# diwali_lights_1.net
KiCad netlist of a schematic drawn in EAGLE
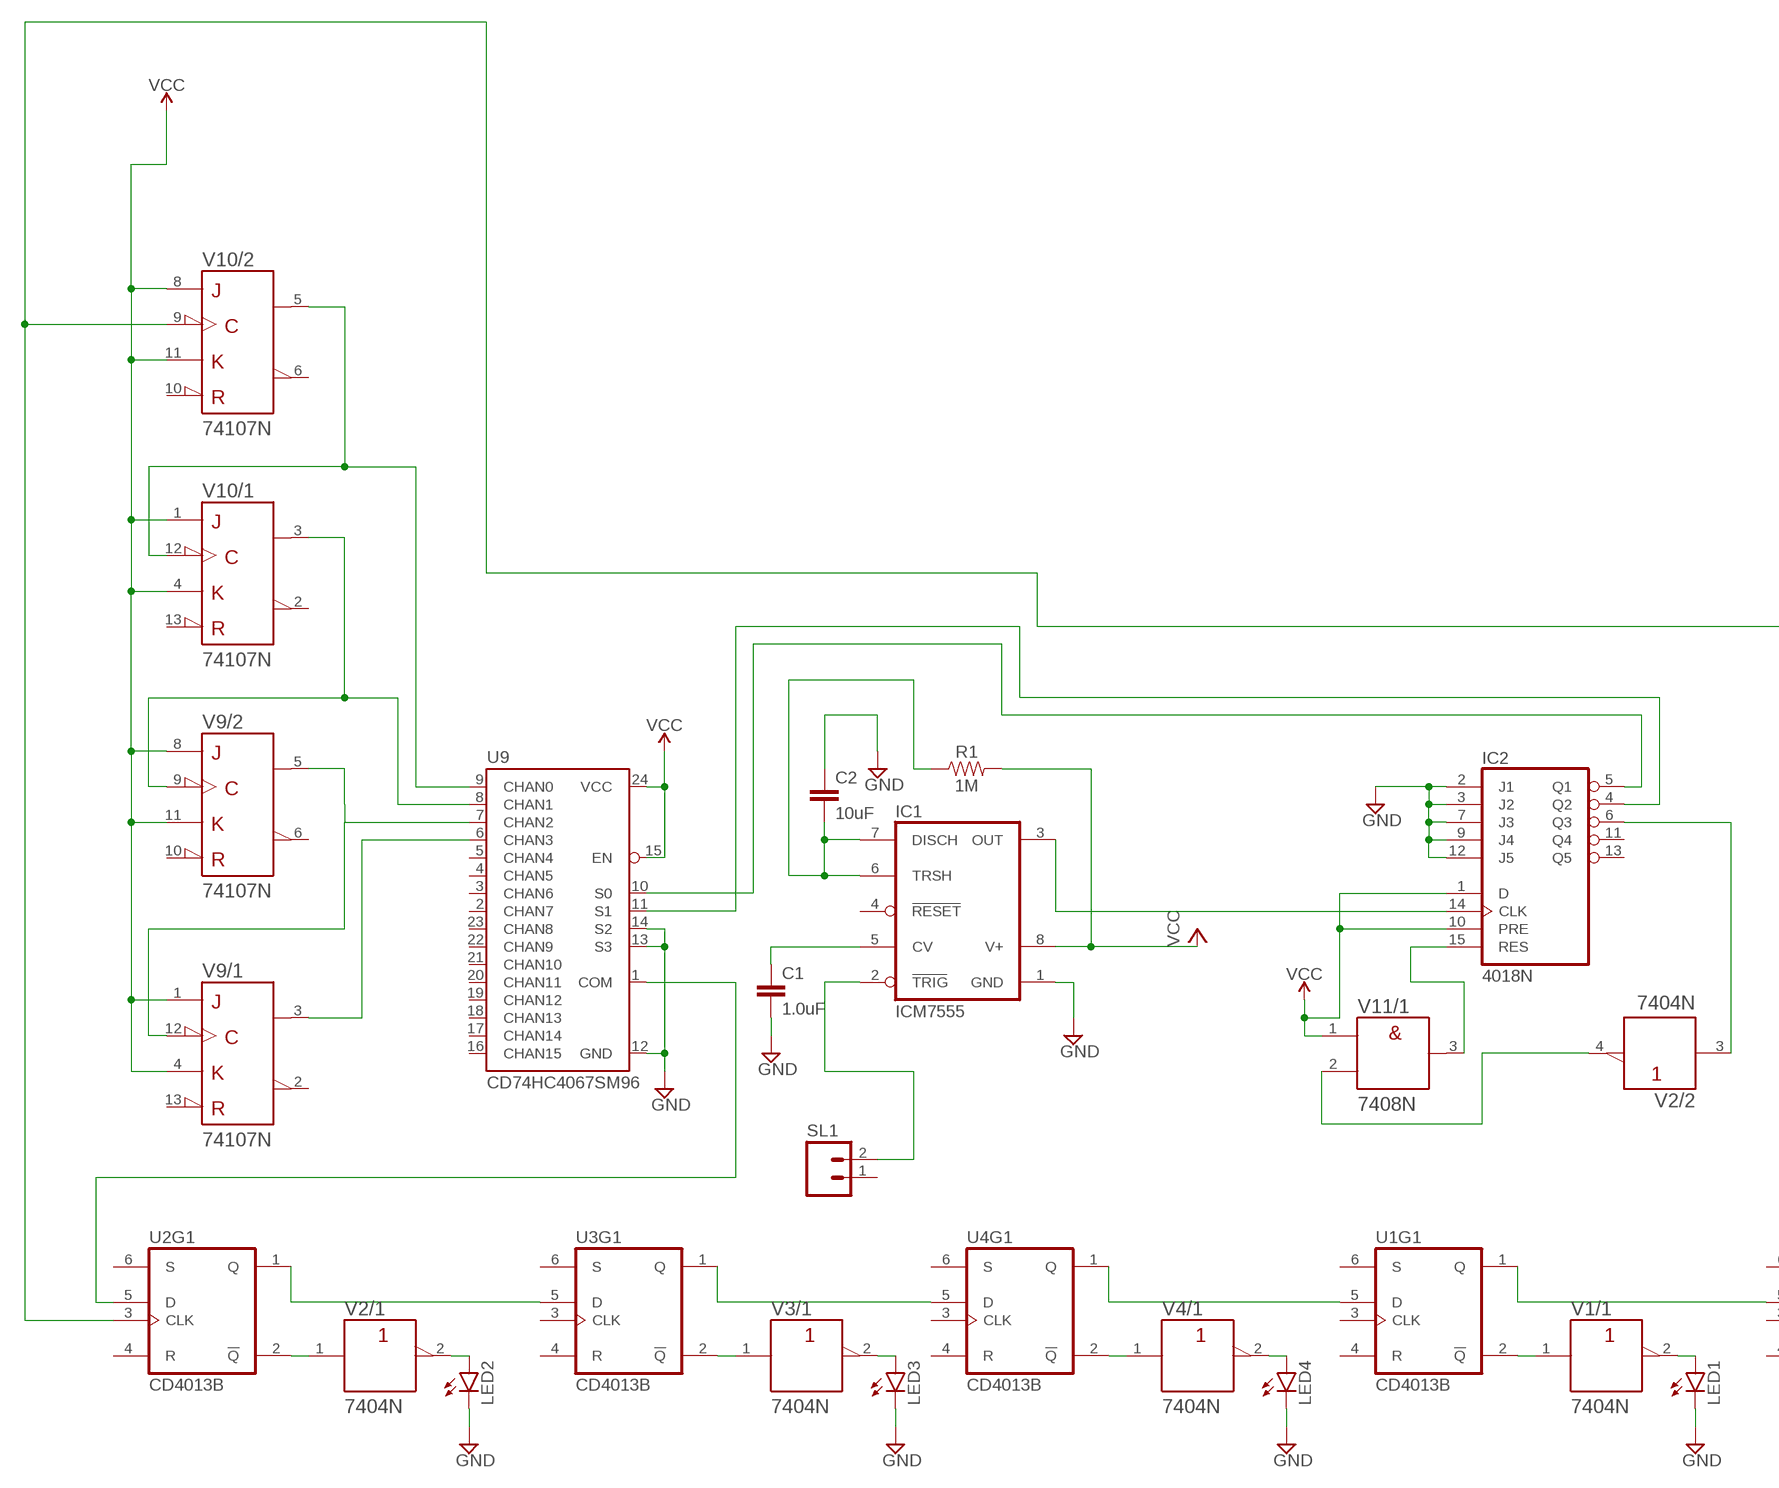
[diagram p0: schematic, sheet 1, part 1 of 2]
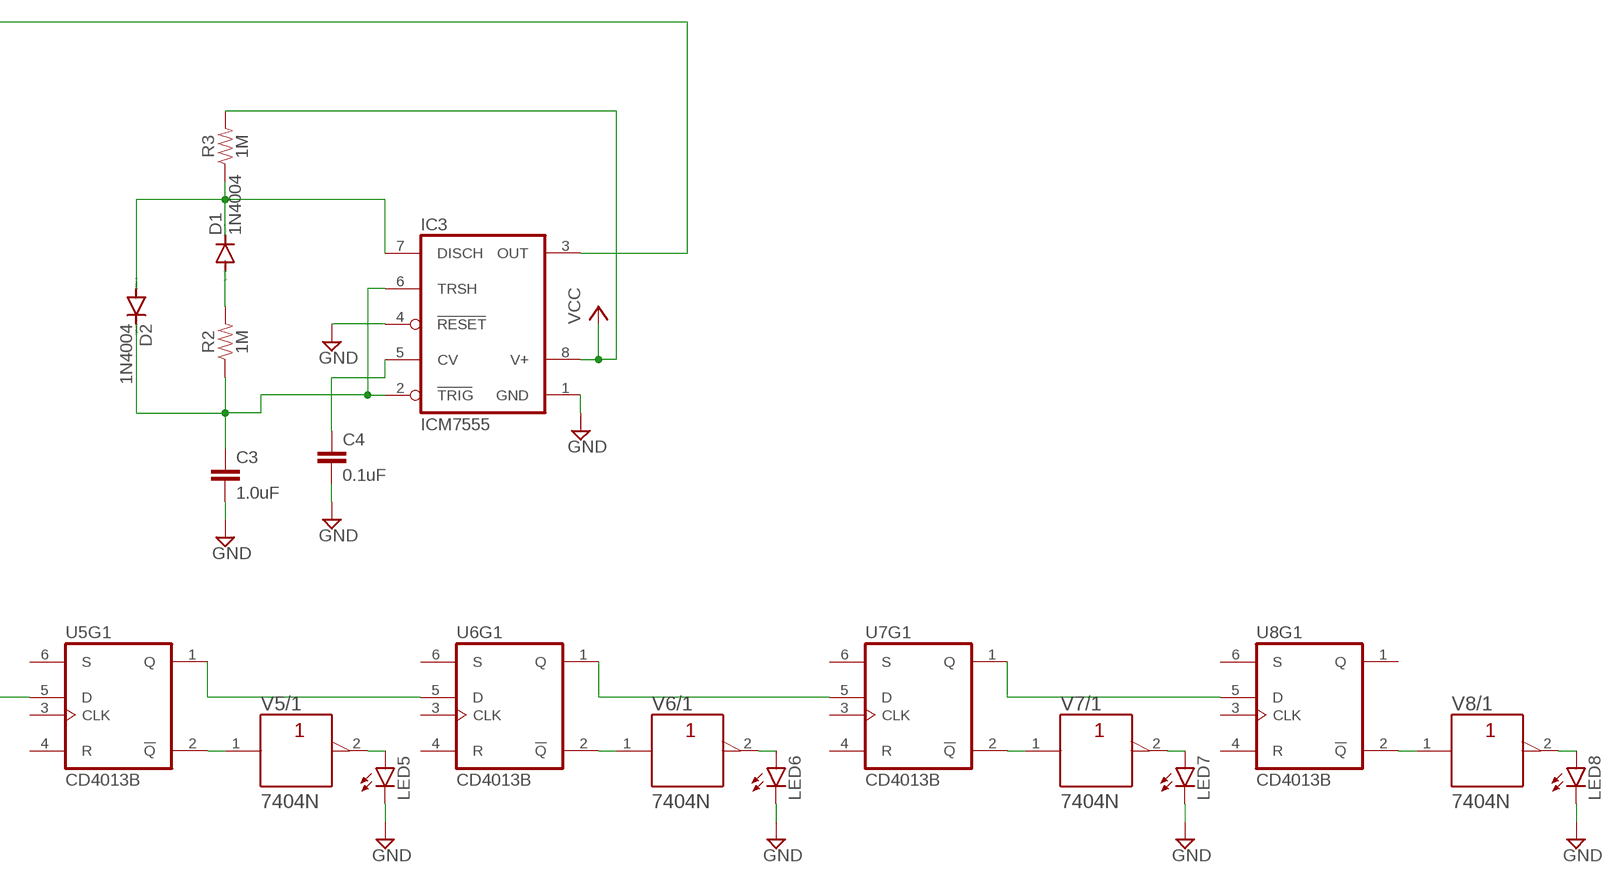
[diagram p1: schematic, sheet 1, part 2 of 2]

(export (version "E")
  (design (tool "Eeschema 10.0.6"))
  (components
    (comp (ref "C1")
      (value "1.0uF")
      (footprint "eagle-import:0402")
      (libsource (lib "eagle-import") (part "1.0UF-0402-16V-10%"))
    )
    (comp (ref "C2")
      (value "10uF")
      (footprint "eagle-import:0805")
      (libsource (lib "eagle-import") (part "10UF-0805-10V-10%"))
    )
    (comp (ref "C3")
      (value "1.0uF")
      (footprint "eagle-import:0402")
      (libsource (lib "eagle-import") (part "1.0UF-0402-16V-10%"))
    )
    (comp (ref "C4")
      (value "0.1uF")
      (footprint "eagle-import:0402")
      (libsource (lib "eagle-import") (part "0.1UF-0402-16V-10%"))
    )
    (comp (ref "D1")
      (value "1N4004")
      (footprint "eagle-import:DO41-10")
      (libsource (lib "eagle-import") (part "1N4004"))
    )
    (comp (ref "D2")
      (value "1N4004")
      (footprint "eagle-import:DO41-10")
      (libsource (lib "eagle-import") (part "1N4004"))
    )
    (comp (ref "IC1")
      (value "ICM7555")
      (footprint "eagle-import:DIL08")
      (fields (field (name "MF") "MAXIM") (field (name "MPN") "ICM7555IPA+"))
      (libsource (lib "eagle-import") (part "ICM7555"))
    )
    (comp (ref "IC2")
      (value "4018N")
      (footprint "eagle-import:DIL16")
      (libsource (lib "eagle-import") (part "4018N"))
    )
    (comp (ref "IC3")
      (value "ICM7555")
      (footprint "eagle-import:DIL08")
      (fields (field (name "MF") "MAXIM") (field (name "MPN") "ICM7555IPA+"))
      (libsource (lib "eagle-import") (part "ICM7555"))
    )
    (comp (ref "LED1")
      (value "LED5MM")
      (footprint "eagle-import:LED5MM")
      (libsource (lib "eagle-import") (part "LED5MM"))
    )
    (comp (ref "LED2")
      (value "LED5MM")
      (footprint "eagle-import:LED5MM")
      (libsource (lib "eagle-import") (part "LED5MM"))
    )
    (comp (ref "LED3")
      (value "LED5MM")
      (footprint "eagle-import:LED5MM")
      (libsource (lib "eagle-import") (part "LED5MM"))
    )
    (comp (ref "LED4")
      (value "LED5MM")
      (footprint "eagle-import:LED5MM")
      (libsource (lib "eagle-import") (part "LED5MM"))
    )
    (comp (ref "LED5")
      (value "LED5MM")
      (footprint "eagle-import:LED5MM")
      (libsource (lib "eagle-import") (part "LED5MM"))
    )
    (comp (ref "LED6")
      (value "LED5MM")
      (footprint "eagle-import:LED5MM")
      (libsource (lib "eagle-import") (part "LED5MM"))
    )
    (comp (ref "LED7")
      (value "LED5MM")
      (footprint "eagle-import:LED5MM")
      (libsource (lib "eagle-import") (part "LED5MM"))
    )
    (comp (ref "LED8")
      (value "LED5MM")
      (footprint "eagle-import:LED5MM")
      (libsource (lib "eagle-import") (part "LED5MM"))
    )
    (comp (ref "R1")
      (value "1M")
      (footprint "eagle-import:0402")
      (libsource (lib "eagle-import") (part "1MOHM-0402-1/16W-5%"))
    )
    (comp (ref "R2")
      (value "1M")
      (footprint "eagle-import:AXIAL-0.3")
      (libsource (lib "eagle-import") (part "1MOHM-HORIZ-1/4W-5%"))
    )
    (comp (ref "R3")
      (value "1M")
      (footprint "eagle-import:AXIAL-0.3")
      (libsource (lib "eagle-import") (part "1MOHM-HORIZ-1/4W-5%"))
    )
    (comp (ref "SL1")
      (value "M02")
      (footprint "eagle-import:02P")
      (libsource (lib "eagle-import") (part "M02"))
    )
    (comp (ref "U1")
      (value "CD4013B")
      (footprint "eagle-import:DIP14-KIT")
      (libsource (lib "eagle-import") (part "CD4013"))
    )
    (comp (ref "U2")
      (value "CD4013B")
      (footprint "eagle-import:DIP14-KIT")
      (libsource (lib "eagle-import") (part "CD4013"))
    )
    (comp (ref "U3")
      (value "CD4013B")
      (footprint "eagle-import:DIP14-KIT")
      (libsource (lib "eagle-import") (part "CD4013"))
    )
    (comp (ref "U4")
      (value "CD4013B")
      (footprint "eagle-import:DIP14-KIT")
      (libsource (lib "eagle-import") (part "CD4013"))
    )
    (comp (ref "U5")
      (value "CD4013B")
      (footprint "eagle-import:DIP14-KIT")
      (libsource (lib "eagle-import") (part "CD4013"))
    )
    (comp (ref "U6")
      (value "CD4013B")
      (footprint "eagle-import:DIP14-KIT")
      (libsource (lib "eagle-import") (part "CD4013"))
    )
    (comp (ref "U7")
      (value "CD4013B")
      (footprint "eagle-import:DIP14-KIT")
      (libsource (lib "eagle-import") (part "CD4013"))
    )
    (comp (ref "U8")
      (value "CD4013B")
      (footprint "eagle-import:DIP14-KIT")
      (libsource (lib "eagle-import") (part "CD4013"))
    )
    (comp (ref "U9")
      (value "CD74HC4067SM96")
      (footprint "eagle-import:SSOP24")
      (libsource (lib "eagle-import") (part "744067SM96HC"))
    )
    (comp (ref "V1")
      (value "7404N")
      (footprint "eagle-import:DIL14")
      (libsource (lib "eagle-import") (part "7404N"))
    )
    (comp (ref "V2")
      (value "7404N")
      (footprint "eagle-import:DIL14")
      (libsource (lib "eagle-import") (part "7404N"))
    )
    (comp (ref "V3")
      (value "7404N")
      (footprint "eagle-import:DIL14")
      (libsource (lib "eagle-import") (part "7404N"))
    )
    (comp (ref "V4")
      (value "7404N")
      (footprint "eagle-import:DIL14")
      (libsource (lib "eagle-import") (part "7404N"))
    )
    (comp (ref "V5")
      (value "7404N")
      (footprint "eagle-import:DIL14")
      (libsource (lib "eagle-import") (part "7404N"))
    )
    (comp (ref "V6")
      (value "7404N")
      (footprint "eagle-import:DIL14")
      (libsource (lib "eagle-import") (part "7404N"))
    )
    (comp (ref "V7")
      (value "7404N")
      (footprint "eagle-import:DIL14")
      (libsource (lib "eagle-import") (part "7404N"))
    )
    (comp (ref "V8")
      (value "7404N")
      (footprint "eagle-import:DIL14")
      (libsource (lib "eagle-import") (part "7404N"))
    )
    (comp (ref "V9")
      (value "74107N")
      (footprint "eagle-import:DIL14")
      (libsource (lib "eagle-import") (part "74107N"))
    )
    (comp (ref "V10")
      (value "74107N")
      (footprint "eagle-import:DIL14")
      (libsource (lib "eagle-import") (part "74107N"))
    )
    (comp (ref "V11")
      (value "7408N")
      (footprint "eagle-import:DIL14")
      (libsource (lib "eagle-import") (part "7408N"))
    )
  )
  (nets
    (net (code "1") (name "GND") (class "Default")
      (node (ref "C1") (pin "2") (pinfunction "2_2") (pintype "passive"))
      (node (ref "C2") (pin "1") (pinfunction "1_1") (pintype "passive"))
      (node (ref "C3") (pin "2") (pinfunction "2_2") (pintype "passive"))
      (node (ref "C4") (pin "2") (pinfunction "2_2") (pintype "passive"))
      (node (ref "IC1") (pin "1") (pinfunction "GND_1") (pintype "power_in"))
      (node (ref "IC2") (pin "12") (pinfunction "J5_12") (pintype "input"))
      (node (ref "IC2") (pin "2") (pinfunction "J1_2") (pintype "input"))
      (node (ref "IC2") (pin "3") (pinfunction "J2_3") (pintype "input"))
      (node (ref "IC2") (pin "7") (pinfunction "J3_7") (pintype "input"))
      (node (ref "IC2") (pin "9") (pinfunction "J4_9") (pintype "input"))
      (node (ref "IC3") (pin "1") (pinfunction "GND_1") (pintype "power_in"))
      (node (ref "IC3") (pin "4") (pinfunction "RESET_4") (pintype "input"))
      (node (ref "LED1") (pin "K") (pinfunction "C_K") (pintype "passive"))
      (node (ref "LED2") (pin "K") (pinfunction "C_K") (pintype "passive"))
      (node (ref "LED3") (pin "K") (pinfunction "C_K") (pintype "passive"))
      (node (ref "LED4") (pin "K") (pinfunction "C_K") (pintype "passive"))
      (node (ref "LED5") (pin "K") (pinfunction "C_K") (pintype "passive"))
      (node (ref "LED6") (pin "K") (pinfunction "C_K") (pintype "passive"))
      (node (ref "LED7") (pin "K") (pinfunction "C_K") (pintype "passive"))
      (node (ref "LED8") (pin "K") (pinfunction "C_K") (pintype "passive"))
      (node (ref "U9") (pin "12") (pinfunction "GND_12") (pintype "bidirectional"))
      (node (ref "U9") (pin "13") (pinfunction "S3_13") (pintype "input"))
      (node (ref "U9") (pin "14") (pinfunction "S2_14") (pintype "input"))
    )
    (net (code "2") (name "Net-(IC1-CV)") (class "Default")
      (node (ref "C1") (pin "1") (pinfunction "1_1") (pintype "passive"))
      (node (ref "IC1") (pin "5") (pinfunction "CV_5") (pintype "passive"))
    )
    (net (code "3") (name "Net-(IC1-DISCH)") (class "Default")
      (node (ref "C2") (pin "2") (pinfunction "2_2") (pintype "passive"))
      (node (ref "IC1") (pin "6") (pinfunction "TRSH_6") (pintype "input"))
      (node (ref "IC1") (pin "7") (pinfunction "DISCH_7") (pintype "input"))
      (node (ref "R1") (pin "1") (pinfunction "1_1") (pintype "passive"))
    )
    (net (code "4") (name "Net-(IC1-OUT)") (class "Default")
      (node (ref "IC1") (pin "3") (pinfunction "OUT_3") (pintype "output"))
      (node (ref "IC2") (pin "14") (pinfunction "CLK_14") (pintype "input"))
    )
    (net (code "5") (name "Net-(IC1-TRIG)") (class "Default")
      (node (ref "IC1") (pin "2") (pinfunction "TRIG_2") (pintype "bidirectional"))
      (node (ref "SL1") (pin "2") (pinfunction "2_2") (pintype "passive"))
    )
    (net (code "6") (name "Net-(IC2A-Q1)") (class "Default")
      (node (ref "IC2") (pin "5") (pinfunction "Q1_5") (pintype "output"))
      (node (ref "U9") (pin "10") (pinfunction "S0_10") (pintype "input"))
    )
    (net (code "7") (name "Net-(IC2A-Q2)") (class "Default")
      (node (ref "IC2") (pin "4") (pinfunction "Q2_4") (pintype "output"))
      (node (ref "U9") (pin "11") (pinfunction "S1_11") (pintype "input"))
    )
    (net (code "8") (name "Net-(IC2A-Q3)") (class "Default")
      (node (ref "IC2") (pin "6") (pinfunction "Q3_6") (pintype "output"))
      (node (ref "V2") (pin "3") (pinfunction "A_3") (pintype "input"))
    )
    (net (code "9") (name "Net-(IC2A-RES)") (class "Default")
      (node (ref "IC2") (pin "15") (pinfunction "RES_15") (pintype "input"))
      (node (ref "V11") (pin "3") (pinfunction "Y_3") (pintype "output"))
    )
    (net (code "10") (name "Net-(IC3-CV)") (class "Default")
      (node (ref "C4") (pin "1") (pinfunction "1_1") (pintype "passive"))
      (node (ref "IC3") (pin "5") (pinfunction "CV_5") (pintype "passive"))
    )
    (net (code "11") (name "Net-(IC3-DISCH)") (class "Default")
      (node (ref "D1") (pin "C") (pinfunction "C_C") (pintype "passive"))
      (node (ref "D2") (pin "A") (pinfunction "A_A") (pintype "passive"))
      (node (ref "IC3") (pin "7") (pinfunction "DISCH_7") (pintype "input"))
      (node (ref "R3") (pin "P$1") (pinfunction "1_P$1") (pintype "passive"))
    )
    (net (code "12") (name "Net-(IC3-OUT)") (class "Default")
      (node (ref "IC3") (pin "3") (pinfunction "OUT_3") (pintype "output"))
      (node (ref "U2") (pin "3") (pinfunction "CLK_3") (pintype "input"))
      (node (ref "V10") (pin "9") (pinfunction "CLK_9") (pintype "input"))
    )
    (net (code "13") (name "Net-(IC3-TRIG)") (class "Default")
      (node (ref "C3") (pin "1") (pinfunction "1_1") (pintype "passive"))
      (node (ref "D2") (pin "C") (pinfunction "C_C") (pintype "passive"))
      (node (ref "IC3") (pin "2") (pinfunction "TRIG_2") (pintype "bidirectional"))
      (node (ref "IC3") (pin "6") (pinfunction "TRSH_6") (pintype "input"))
      (node (ref "R2") (pin "P$1") (pinfunction "1_P$1") (pintype "passive"))
    )
    (net (code "14") (name "Net-(R2-2)") (class "Default")
      (node (ref "D1") (pin "A") (pinfunction "A_A") (pintype "passive"))
      (node (ref "R2") (pin "P$2") (pinfunction "2_P$2") (pintype "passive"))
    )
    (net (code "15") (name "Net-(U1A-D)") (class "Default")
      (node (ref "U1") (pin "5") (pinfunction "D_5") (pintype "input"))
      (node (ref "U4") (pin "1") (pinfunction "Q_1") (pintype "output"))
    )
    (net (code "16") (name "Net-(U1A-Q)") (class "Default")
      (node (ref "U1") (pin "1") (pinfunction "Q_1") (pintype "output"))
      (node (ref "U5") (pin "5") (pinfunction "D_5") (pintype "input"))
    )
    (net (code "17") (name "Net-(U1A-~{Q})") (class "Default")
      (node (ref "U1") (pin "2") (pinfunction "~{Q}_2") (pintype "output"))
      (node (ref "V1") (pin "1") (pinfunction "A_1") (pintype "input"))
    )
    (net (code "18") (name "Net-(U2A-D)") (class "Default")
      (node (ref "U2") (pin "5") (pinfunction "D_5") (pintype "input"))
      (node (ref "U9") (pin "1") (pinfunction "COM_1") (pintype "bidirectional"))
    )
    (net (code "19") (name "Net-(U2A-Q)") (class "Default")
      (node (ref "U2") (pin "1") (pinfunction "Q_1") (pintype "output"))
      (node (ref "U3") (pin "5") (pinfunction "D_5") (pintype "input"))
    )
    (net (code "20") (name "Net-(U2A-~{Q})") (class "Default")
      (node (ref "U2") (pin "2") (pinfunction "~{Q}_2") (pintype "output"))
      (node (ref "V2") (pin "1") (pinfunction "A_1") (pintype "input"))
    )
    (net (code "21") (name "Net-(U3A-Q)") (class "Default")
      (node (ref "U3") (pin "1") (pinfunction "Q_1") (pintype "output"))
      (node (ref "U4") (pin "5") (pinfunction "D_5") (pintype "input"))
    )
    (net (code "22") (name "Net-(U3A-~{Q})") (class "Default")
      (node (ref "U3") (pin "2") (pinfunction "~{Q}_2") (pintype "output"))
      (node (ref "V3") (pin "1") (pinfunction "A_1") (pintype "input"))
    )
    (net (code "23") (name "Net-(U4A-~{Q})") (class "Default")
      (node (ref "U4") (pin "2") (pinfunction "~{Q}_2") (pintype "output"))
      (node (ref "V4") (pin "1") (pinfunction "A_1") (pintype "input"))
    )
    (net (code "24") (name "Net-(U5A-Q)") (class "Default")
      (node (ref "U5") (pin "1") (pinfunction "Q_1") (pintype "output"))
      (node (ref "U6") (pin "5") (pinfunction "D_5") (pintype "input"))
    )
    (net (code "25") (name "Net-(U5A-~{Q})") (class "Default")
      (node (ref "U5") (pin "2") (pinfunction "~{Q}_2") (pintype "output"))
      (node (ref "V5") (pin "1") (pinfunction "A_1") (pintype "input"))
    )
    (net (code "26") (name "Net-(U6A-Q)") (class "Default")
      (node (ref "U6") (pin "1") (pinfunction "Q_1") (pintype "output"))
      (node (ref "U7") (pin "5") (pinfunction "D_5") (pintype "input"))
    )
    (net (code "27") (name "Net-(U6A-~{Q})") (class "Default")
      (node (ref "U6") (pin "2") (pinfunction "~{Q}_2") (pintype "output"))
      (node (ref "V6") (pin "1") (pinfunction "A_1") (pintype "input"))
    )
    (net (code "28") (name "Net-(U7A-Q)") (class "Default")
      (node (ref "U7") (pin "1") (pinfunction "Q_1") (pintype "output"))
      (node (ref "U8") (pin "5") (pinfunction "D_5") (pintype "input"))
    )
    (net (code "29") (name "Net-(U7A-~{Q})") (class "Default")
      (node (ref "U7") (pin "2") (pinfunction "~{Q}_2") (pintype "output"))
      (node (ref "V7") (pin "1") (pinfunction "A_1") (pintype "input"))
    )
    (net (code "30") (name "Net-(U8A-~{Q})") (class "Default")
      (node (ref "U8") (pin "2") (pinfunction "~{Q}_2") (pintype "output"))
      (node (ref "V8") (pin "1") (pinfunction "A_1") (pintype "input"))
    )
    (net (code "31") (name "Net-(U9-CHAN0)") (class "Default")
      (node (ref "U9") (pin "9") (pinfunction "CHAN0_9") (pintype "bidirectional"))
      (node (ref "V10") (pin "12") (pinfunction "CLK_12") (pintype "input"))
      (node (ref "V10") (pin "5") (pinfunction "Q_5") (pintype "output"))
    )
    (net (code "32") (name "Net-(U9-CHAN1)") (class "Default")
      (node (ref "U9") (pin "8") (pinfunction "CHAN1_8") (pintype "bidirectional"))
      (node (ref "V10") (pin "3") (pinfunction "Q_3") (pintype "output"))
      (node (ref "V9") (pin "9") (pinfunction "CLK_9") (pintype "input"))
    )
    (net (code "33") (name "Net-(U9-CHAN2)") (class "Default")
      (node (ref "U9") (pin "7") (pinfunction "CHAN2_7") (pintype "bidirectional"))
      (node (ref "V9") (pin "12") (pinfunction "CLK_12") (pintype "input"))
      (node (ref "V9") (pin "5") (pinfunction "Q_5") (pintype "output"))
    )
    (net (code "34") (name "Net-(U9-CHAN3)") (class "Default")
      (node (ref "U9") (pin "6") (pinfunction "CHAN3_6") (pintype "bidirectional"))
      (node (ref "V9") (pin "3") (pinfunction "Q_3") (pintype "output"))
    )
    (net (code "35") (name "Net-(V1C-Y)") (class "Default")
      (node (ref "LED1") (pin "A") (pinfunction "A_A") (pintype "passive"))
      (node (ref "V1") (pin "2") (pinfunction "Y_2") (pintype "output"))
    )
    (net (code "36") (name "Net-(V2C-Y)") (class "Default")
      (node (ref "LED2") (pin "A") (pinfunction "A_A") (pintype "passive"))
      (node (ref "V2") (pin "2") (pinfunction "Y_2") (pintype "output"))
    )
    (net (code "37") (name "Net-(V3C-Y)") (class "Default")
      (node (ref "LED3") (pin "A") (pinfunction "A_A") (pintype "passive"))
      (node (ref "V3") (pin "2") (pinfunction "Y_2") (pintype "output"))
    )
    (net (code "38") (name "Net-(V4C-Y)") (class "Default")
      (node (ref "LED4") (pin "A") (pinfunction "A_A") (pintype "passive"))
      (node (ref "V4") (pin "2") (pinfunction "Y_2") (pintype "output"))
    )
    (net (code "39") (name "Net-(V5C-Y)") (class "Default")
      (node (ref "LED5") (pin "A") (pinfunction "A_A") (pintype "passive"))
      (node (ref "V5") (pin "2") (pinfunction "Y_2") (pintype "output"))
    )
    (net (code "40") (name "Net-(V6C-Y)") (class "Default")
      (node (ref "LED6") (pin "A") (pinfunction "A_A") (pintype "passive"))
      (node (ref "V6") (pin "2") (pinfunction "Y_2") (pintype "output"))
    )
    (net (code "41") (name "Net-(V7C-Y)") (class "Default")
      (node (ref "LED7") (pin "A") (pinfunction "A_A") (pintype "passive"))
      (node (ref "V7") (pin "2") (pinfunction "Y_2") (pintype "output"))
    )
    (net (code "42") (name "Net-(V8C-Y)") (class "Default")
      (node (ref "LED8") (pin "A") (pinfunction "A_A") (pintype "passive"))
      (node (ref "V8") (pin "2") (pinfunction "Y_2") (pintype "output"))
    )
    (net (code "43") (name "Net-(V11C-B)") (class "Default")
      (node (ref "V11") (pin "2") (pinfunction "B_2") (pintype "input"))
      (node (ref "V2") (pin "4") (pinfunction "Y_4") (pintype "output"))
    )
    (net (code "44") (name "VCC") (class "Default")
      (node (ref "IC1") (pin "8") (pinfunction "V+_8") (pintype "power_in"))
      (node (ref "IC2") (pin "1") (pinfunction "D_1") (pintype "input"))
      (node (ref "IC2") (pin "10") (pinfunction "PRE_10") (pintype "input"))
      (node (ref "IC3") (pin "8") (pinfunction "V+_8") (pintype "power_in"))
      (node (ref "R1") (pin "2") (pinfunction "2_2") (pintype "passive"))
      (node (ref "R3") (pin "P$2") (pinfunction "2_P$2") (pintype "passive"))
      (node (ref "U9") (pin "15") (pinfunction "EN_15") (pintype "input"))
      (node (ref "U9") (pin "24") (pinfunction "VCC_24") (pintype "bidirectional"))
      (node (ref "V10") (pin "1") (pinfunction "J_1") (pintype "input"))
      (node (ref "V10") (pin "11") (pinfunction "K_11") (pintype "input"))
      (node (ref "V10") (pin "4") (pinfunction "K_4") (pintype "input"))
      (node (ref "V10") (pin "8") (pinfunction "J_8") (pintype "input"))
      (node (ref "V11") (pin "1") (pinfunction "A_1") (pintype "input"))
      (node (ref "V9") (pin "1") (pinfunction "J_1") (pintype "input"))
      (node (ref "V9") (pin "11") (pinfunction "K_11") (pintype "input"))
      (node (ref "V9") (pin "4") (pinfunction "K_4") (pintype "input"))
      (node (ref "V9") (pin "8") (pinfunction "J_8") (pintype "input"))
    )
    (net (code "45") (name "unconnected-(IC1-RESET-Pad4)") (class "Default")
      (node (ref "IC1") (pin "4") (pinfunction "RESET_4") (pintype "input"))
    )
    (net (code "46") (name "unconnected-(IC2A-Q4-Pad11)") (class "Default")
      (node (ref "IC2") (pin "11") (pinfunction "Q4_11") (pintype "output"))
    )
    (net (code "47") (name "unconnected-(IC2A-Q5-Pad13)") (class "Default")
      (node (ref "IC2") (pin "13") (pinfunction "Q5_13") (pintype "output"))
    )
    (net (code "48") (name "unconnected-(SL1-Pad1)") (class "Default")
      (node (ref "SL1") (pin "1") (pinfunction "1_1") (pintype "passive"))
    )
    (net (code "49") (name "unconnected-(U1A-CLK-Pad3)") (class "Default")
      (node (ref "U1") (pin "3") (pinfunction "CLK_3") (pintype "input"))
    )
    (net (code "50") (name "unconnected-(U1A-R-Pad4)") (class "Default")
      (node (ref "U1") (pin "4") (pinfunction "R_4") (pintype "input"))
    )
    (net (code "51") (name "unconnected-(U1A-S-Pad6)") (class "Default")
      (node (ref "U1") (pin "6") (pinfunction "S_6") (pintype "input"))
    )
    (net (code "52") (name "unconnected-(U2A-R-Pad4)") (class "Default")
      (node (ref "U2") (pin "4") (pinfunction "R_4") (pintype "input"))
    )
    (net (code "53") (name "unconnected-(U2A-S-Pad6)") (class "Default")
      (node (ref "U2") (pin "6") (pinfunction "S_6") (pintype "input"))
    )
    (net (code "54") (name "unconnected-(U3A-CLK-Pad3)") (class "Default")
      (node (ref "U3") (pin "3") (pinfunction "CLK_3") (pintype "input"))
    )
    (net (code "55") (name "unconnected-(U3A-R-Pad4)") (class "Default")
      (node (ref "U3") (pin "4") (pinfunction "R_4") (pintype "input"))
    )
    (net (code "56") (name "unconnected-(U3A-S-Pad6)") (class "Default")
      (node (ref "U3") (pin "6") (pinfunction "S_6") (pintype "input"))
    )
    (net (code "57") (name "unconnected-(U4A-CLK-Pad3)") (class "Default")
      (node (ref "U4") (pin "3") (pinfunction "CLK_3") (pintype "input"))
    )
    (net (code "58") (name "unconnected-(U4A-R-Pad4)") (class "Default")
      (node (ref "U4") (pin "4") (pinfunction "R_4") (pintype "input"))
    )
    (net (code "59") (name "unconnected-(U4A-S-Pad6)") (class "Default")
      (node (ref "U4") (pin "6") (pinfunction "S_6") (pintype "input"))
    )
    (net (code "60") (name "unconnected-(U5A-CLK-Pad3)") (class "Default")
      (node (ref "U5") (pin "3") (pinfunction "CLK_3") (pintype "input"))
    )
    (net (code "61") (name "unconnected-(U5A-R-Pad4)") (class "Default")
      (node (ref "U5") (pin "4") (pinfunction "R_4") (pintype "input"))
    )
    (net (code "62") (name "unconnected-(U5A-S-Pad6)") (class "Default")
      (node (ref "U5") (pin "6") (pinfunction "S_6") (pintype "input"))
    )
    (net (code "63") (name "unconnected-(U6A-CLK-Pad3)") (class "Default")
      (node (ref "U6") (pin "3") (pinfunction "CLK_3") (pintype "input"))
    )
    (net (code "64") (name "unconnected-(U6A-R-Pad4)") (class "Default")
      (node (ref "U6") (pin "4") (pinfunction "R_4") (pintype "input"))
    )
    (net (code "65") (name "unconnected-(U6A-S-Pad6)") (class "Default")
      (node (ref "U6") (pin "6") (pinfunction "S_6") (pintype "input"))
    )
    (net (code "66") (name "unconnected-(U7A-CLK-Pad3)") (class "Default")
      (node (ref "U7") (pin "3") (pinfunction "CLK_3") (pintype "input"))
    )
    (net (code "67") (name "unconnected-(U7A-R-Pad4)") (class "Default")
      (node (ref "U7") (pin "4") (pinfunction "R_4") (pintype "input"))
    )
    (net (code "68") (name "unconnected-(U7A-S-Pad6)") (class "Default")
      (node (ref "U7") (pin "6") (pinfunction "S_6") (pintype "input"))
    )
    (net (code "69") (name "unconnected-(U8A-CLK-Pad3)") (class "Default")
      (node (ref "U8") (pin "3") (pinfunction "CLK_3") (pintype "input"))
    )
    (net (code "70") (name "unconnected-(U8A-Q-Pad1)") (class "Default")
      (node (ref "U8") (pin "1") (pinfunction "Q_1") (pintype "output"))
    )
    (net (code "71") (name "unconnected-(U8A-R-Pad4)") (class "Default")
      (node (ref "U8") (pin "4") (pinfunction "R_4") (pintype "input"))
    )
    (net (code "72") (name "unconnected-(U8A-S-Pad6)") (class "Default")
      (node (ref "U8") (pin "6") (pinfunction "S_6") (pintype "input"))
    )
    (net (code "73") (name "unconnected-(U9-CHAN4-Pad5)") (class "Default")
      (node (ref "U9") (pin "5") (pinfunction "CHAN4_5") (pintype "bidirectional"))
    )
    (net (code "74") (name "unconnected-(U9-CHAN5-Pad4)") (class "Default")
      (node (ref "U9") (pin "4") (pinfunction "CHAN5_4") (pintype "bidirectional"))
    )
    (net (code "75") (name "unconnected-(U9-CHAN6-Pad3)") (class "Default")
      (node (ref "U9") (pin "3") (pinfunction "CHAN6_3") (pintype "bidirectional"))
    )
    (net (code "76") (name "unconnected-(U9-CHAN7-Pad2)") (class "Default")
      (node (ref "U9") (pin "2") (pinfunction "CHAN7_2") (pintype "bidirectional"))
    )
    (net (code "77") (name "unconnected-(U9-CHAN8-Pad23)") (class "Default")
      (node (ref "U9") (pin "23") (pinfunction "CHAN8_23") (pintype "bidirectional"))
    )
    (net (code "78") (name "unconnected-(U9-CHAN9-Pad22)") (class "Default")
      (node (ref "U9") (pin "22") (pinfunction "CHAN9_22") (pintype "bidirectional"))
    )
    (net (code "79") (name "unconnected-(U9-CHAN10-Pad21)") (class "Default")
      (node (ref "U9") (pin "21") (pinfunction "CHAN10_21") (pintype "bidirectional"))
    )
    (net (code "80") (name "unconnected-(U9-CHAN11-Pad20)") (class "Default")
      (node (ref "U9") (pin "20") (pinfunction "CHAN11_20") (pintype "bidirectional"))
    )
    (net (code "81") (name "unconnected-(U9-CHAN12-Pad19)") (class "Default")
      (node (ref "U9") (pin "19") (pinfunction "CHAN12_19") (pintype "bidirectional"))
    )
    (net (code "82") (name "unconnected-(U9-CHAN13-Pad18)") (class "Default")
      (node (ref "U9") (pin "18") (pinfunction "CHAN13_18") (pintype "bidirectional"))
    )
    (net (code "83") (name "unconnected-(U9-CHAN14-Pad17)") (class "Default")
      (node (ref "U9") (pin "17") (pinfunction "CHAN14_17") (pintype "bidirectional"))
    )
    (net (code "84") (name "unconnected-(U9-CHAN15-Pad16)") (class "Default")
      (node (ref "U9") (pin "16") (pinfunction "CHAN15_16") (pintype "bidirectional"))
    )
    (net (code "85") (name "unconnected-(V9C-~{CLR}-Pad13)") (class "Default")
      (node (ref "V9") (pin "13") (pinfunction "~{CLR}_13") (pintype "input"))
    )
    (net (code "86") (name "unconnected-(V9C-~{Q}-Pad2)") (class "Default")
      (node (ref "V9") (pin "2") (pinfunction "~{Q}_2") (pintype "output"))
    )
    (net (code "87") (name "unconnected-(V9D-~{CLR}-Pad10)") (class "Default")
      (node (ref "V9") (pin "10") (pinfunction "~{CLR}_10") (pintype "input"))
    )
    (net (code "88") (name "unconnected-(V9D-~{Q}-Pad6)") (class "Default")
      (node (ref "V9") (pin "6") (pinfunction "~{Q}_6") (pintype "output"))
    )
    (net (code "89") (name "unconnected-(V10C-~{CLR}-Pad13)") (class "Default")
      (node (ref "V10") (pin "13") (pinfunction "~{CLR}_13") (pintype "input"))
    )
    (net (code "90") (name "unconnected-(V10C-~{Q}-Pad2)") (class "Default")
      (node (ref "V10") (pin "2") (pinfunction "~{Q}_2") (pintype "output"))
    )
    (net (code "91") (name "unconnected-(V10D-~{CLR}-Pad10)") (class "Default")
      (node (ref "V10") (pin "10") (pinfunction "~{CLR}_10") (pintype "input"))
    )
    (net (code "92") (name "unconnected-(V10D-~{Q}-Pad6)") (class "Default")
      (node (ref "V10") (pin "6") (pinfunction "~{Q}_6") (pintype "output"))
    )
  )
)
